# PSU_NCP630SET_1V2.net
KiCad netlist of a schematic drawn in Altium Designer
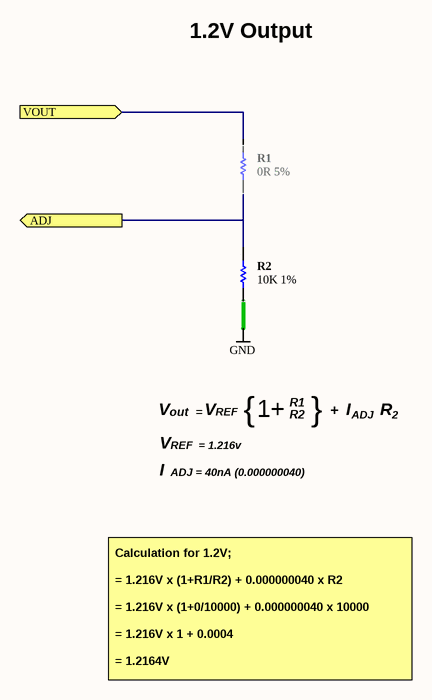
[diagram p0: PSU_NCP630SET_1V2.SchDoc]

(export (version "E")
  (design (tool "Eeschema 10.0.6"))
  (components
    (comp (ref "R1")
      (value "0R 5%")
      (footprint "RESC1005-STAR")
      (description "Resistor, 0R 5% 0402 (1005)")
      (fields (field (name "TOLERANCE") "5%"))
      (libsource (lib "AltiumDesignLibrary") (part "RES"))
    )
    (comp (ref "R2")
      (value "10K 1%")
      (footprint "RESC1005-STAR")
      (description "Resistor, 10K 1% 0402 (1005)")
      (fields (field (name "TOLERANCE") "1 %"))
      (libsource (lib "AltiumDesignLibrary") (part "RES"))
    )
  )
  (nets
    (net (code "1") (name "/ADJ") (class "Default")
      (node (ref "R1") (pin "1") (pinfunction "1_1") (pintype "passive"))
      (node (ref "R2") (pin "1") (pinfunction "1_1") (pintype "passive"))
    )
    (net (code "2") (name "/VOUT") (class "Default")
      (node (ref "R1") (pin "2") (pinfunction "2_2") (pintype "passive"))
    )
    (net (code "3") (name "GND") (class "Default")
      (node (ref "R2") (pin "2") (pinfunction "2_2") (pintype "passive"))
    )
  )
)
